# Embedded.net
KiCad netlist of a schematic drawn in EAGLE
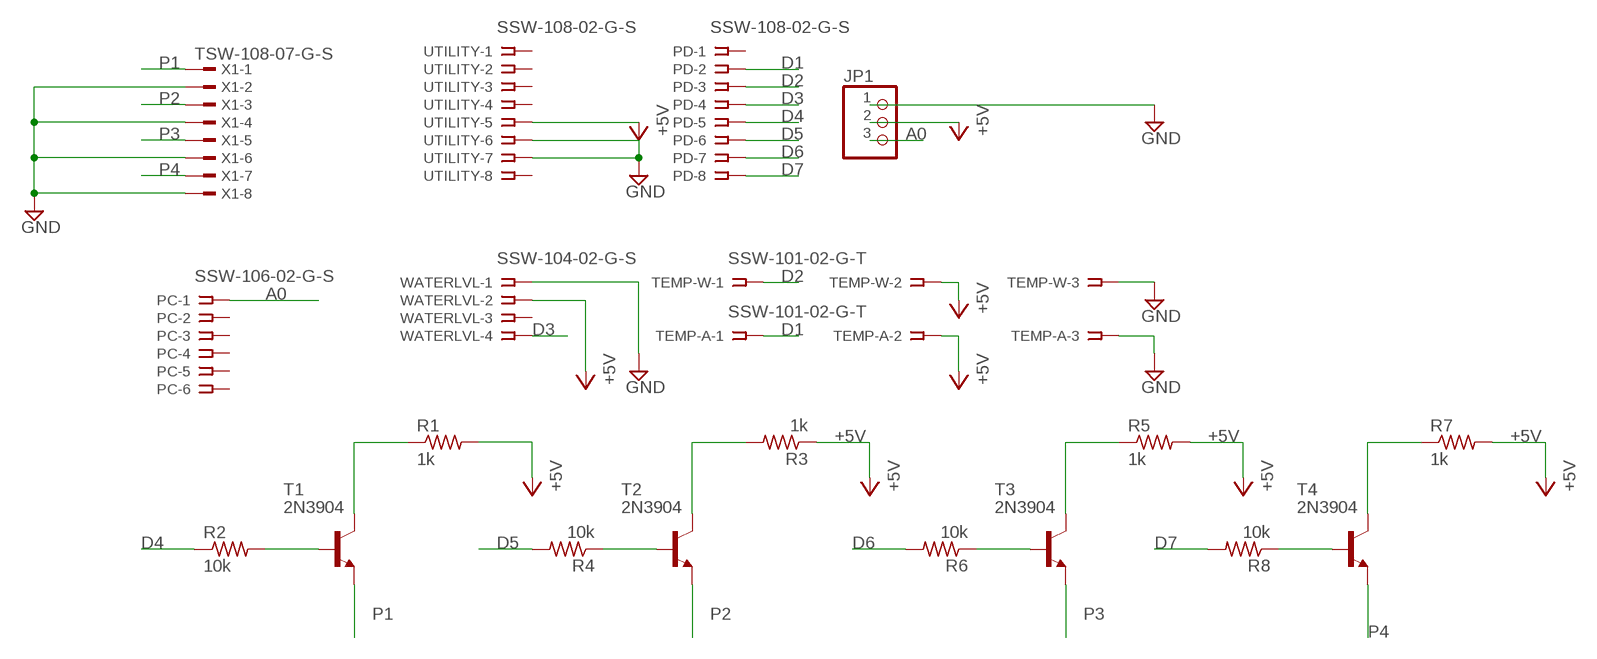
[diagram p0: schematic, sheet 1]

(export (version "E")
  (design (tool "Eeschema 10.0.6"))
  (components
    (comp (ref "JP1")
      (value "PINHD-1X3")
      (footprint "eagle-import:1X03")
      (libsource (lib "eagle-import") (part "PINHD-1X3"))
    )
    (comp (ref "PC")
      (value "SSW-106-02-G-S")
      (footprint "eagle-import:SSW-106-02-G-S")
      (fields (field (name "MF") "Samtec Inc."))
      (libsource (lib "eagle-import") (part "SSW-106-02-G-S"))
    )
    (comp (ref "PD")
      (value "SSW-108-02-G-S")
      (footprint "eagle-import:SSW-108-02-G-S")
      (fields (field (name "MF") "Samtec Inc."))
      (libsource (lib "eagle-import") (part "SSW-108-02-G-S"))
    )
    (comp (ref "R1")
      (value "1k")
      (footprint "eagle-import:0411_15")
      (libsource (lib "eagle-import") (part "RESISTOR"))
    )
    (comp (ref "R2")
      (value "10k")
      (footprint "eagle-import:0411_15")
      (libsource (lib "eagle-import") (part "RESISTOR"))
    )
    (comp (ref "R3")
      (value "1k")
      (footprint "eagle-import:0411_15")
      (libsource (lib "eagle-import") (part "RESISTOR"))
    )
    (comp (ref "R4")
      (value "10k")
      (footprint "eagle-import:0411_15")
      (libsource (lib "eagle-import") (part "RESISTOR"))
    )
    (comp (ref "R5")
      (value "1k")
      (footprint "eagle-import:0411_15")
      (libsource (lib "eagle-import") (part "RESISTOR"))
    )
    (comp (ref "R6")
      (value "10k")
      (footprint "eagle-import:0411_15")
      (libsource (lib "eagle-import") (part "RESISTOR"))
    )
    (comp (ref "R7")
      (value "1k")
      (footprint "eagle-import:0411_15")
      (libsource (lib "eagle-import") (part "RESISTOR"))
    )
    (comp (ref "R8")
      (value "10k")
      (footprint "eagle-import:0411_15")
      (libsource (lib "eagle-import") (part "RESISTOR"))
    )
    (comp (ref "T1")
      (value "2N3904")
      (footprint "eagle-import:TO92")
      (libsource (lib "eagle-import") (part "2N3904"))
    )
    (comp (ref "T2")
      (value "2N3904")
      (footprint "eagle-import:TO92")
      (libsource (lib "eagle-import") (part "2N3904"))
    )
    (comp (ref "T3")
      (value "2N3904")
      (footprint "eagle-import:TO92")
      (libsource (lib "eagle-import") (part "2N3904"))
    )
    (comp (ref "T4")
      (value "2N3904")
      (footprint "eagle-import:TO92")
      (libsource (lib "eagle-import") (part "2N3904"))
    )
    (comp (ref "TEMP-A")
      (value "SSW-101-02-G-T")
      (footprint "eagle-import:SSW-101-02-G-T")
      (fields (field (name "MF") "Samtec Inc."))
      (libsource (lib "eagle-import") (part "SSW-101-02-G-T"))
    )
    (comp (ref "TEMP-W")
      (value "SSW-101-02-G-T")
      (footprint "eagle-import:SSW-101-02-G-T")
      (fields (field (name "MF") "Samtec Inc."))
      (libsource (lib "eagle-import") (part "SSW-101-02-G-T"))
    )
    (comp (ref "UTILITY")
      (value "SSW-108-02-G-S")
      (footprint "eagle-import:SSW-108-02-G-S")
      (fields (field (name "MF") "Samtec Inc."))
      (libsource (lib "eagle-import") (part "SSW-108-02-G-S"))
    )
    (comp (ref "WATERLVL")
      (value "SSW-104-02-G-S")
      (footprint "eagle-import:SSW-104-02-G-S")
      (fields (field (name "MF") "Samtec Inc."))
      (libsource (lib "eagle-import") (part "SSW-104-02-G-S"))
    )
    (comp (ref "X1")
      (value "TSW-108-07-G-S")
      (footprint "eagle-import:TSW-108-XX-G-S")
      (fields (field (name "MF") "Samtec Inc."))
      (libsource (lib "eagle-import") (part "TSW-108--G-S07"))
    )
  )
  (nets
    (net (code "1") (name "+5V") (class "Default")
      (node (ref "JP1") (pin "2") (pinfunction "2_2") (pintype "passive"))
      (node (ref "R1") (pin "2") (pinfunction "2_2") (pintype "passive"))
      (node (ref "R3") (pin "1") (pinfunction "1_1") (pintype "passive"))
      (node (ref "R5") (pin "2") (pinfunction "2_2") (pintype "passive"))
      (node (ref "R7") (pin "2") (pinfunction "2_2") (pintype "passive"))
      (node (ref "TEMP-A") (pin "2") (pinfunction "1_2") (pintype "passive"))
      (node (ref "TEMP-W") (pin "2") (pinfunction "1_2") (pintype "passive"))
      (node (ref "UTILITY") (pin "5") (pinfunction "1_5") (pintype "passive"))
      (node (ref "WATERLVL") (pin "2") (pinfunction "1_2") (pintype "passive"))
    )
    (net (code "2") (name "/A0") (class "Default")
      (node (ref "JP1") (pin "3") (pinfunction "3_3") (pintype "passive"))
      (node (ref "PC") (pin "1") (pinfunction "1_1") (pintype "passive"))
    )
    (net (code "3") (name "/D1") (class "Default")
      (node (ref "PD") (pin "2") (pinfunction "1_2") (pintype "passive"))
      (node (ref "TEMP-A") (pin "1") (pinfunction "1_1") (pintype "passive"))
    )
    (net (code "4") (name "/D2") (class "Default")
      (node (ref "PD") (pin "3") (pinfunction "1_3") (pintype "passive"))
      (node (ref "TEMP-W") (pin "1") (pinfunction "1_1") (pintype "passive"))
    )
    (net (code "5") (name "/D3") (class "Default")
      (node (ref "PD") (pin "4") (pinfunction "1_4") (pintype "passive"))
      (node (ref "WATERLVL") (pin "4") (pinfunction "1_4") (pintype "passive"))
    )
    (net (code "6") (name "/D4") (class "Default")
      (node (ref "PD") (pin "5") (pinfunction "1_5") (pintype "passive"))
      (node (ref "R2") (pin "1") (pinfunction "1_1") (pintype "passive"))
    )
    (net (code "7") (name "/D5") (class "Default")
      (node (ref "PD") (pin "6") (pinfunction "1_6") (pintype "passive"))
      (node (ref "R4") (pin "2") (pinfunction "2_2") (pintype "passive"))
    )
    (net (code "8") (name "/D6") (class "Default")
      (node (ref "PD") (pin "7") (pinfunction "1_7") (pintype "passive"))
      (node (ref "R6") (pin "2") (pinfunction "2_2") (pintype "passive"))
    )
    (net (code "9") (name "/D7") (class "Default")
      (node (ref "PD") (pin "8") (pinfunction "1_8") (pintype "passive"))
      (node (ref "R8") (pin "2") (pinfunction "2_2") (pintype "passive"))
    )
    (net (code "10") (name "/P1") (class "Default")
      (node (ref "T1") (pin "3") (pinfunction "E_3") (pintype "passive"))
      (node (ref "X1") (pin "1") (pinfunction "1_1") (pintype "passive"))
    )
    (net (code "11") (name "/P2") (class "Default")
      (node (ref "T2") (pin "3") (pinfunction "E_3") (pintype "passive"))
      (node (ref "X1") (pin "3") (pinfunction "1_3") (pintype "passive"))
    )
    (net (code "12") (name "/P3") (class "Default")
      (node (ref "T3") (pin "3") (pinfunction "E_3") (pintype "passive"))
      (node (ref "X1") (pin "5") (pinfunction "1_5") (pintype "passive"))
    )
    (net (code "13") (name "/P4") (class "Default")
      (node (ref "T4") (pin "3") (pinfunction "E_3") (pintype "passive"))
      (node (ref "X1") (pin "7") (pinfunction "1_7") (pintype "passive"))
    )
    (net (code "14") (name "GND") (class "Default")
      (node (ref "JP1") (pin "1") (pinfunction "1_1") (pintype "passive"))
      (node (ref "TEMP-A") (pin "3") (pinfunction "1_3") (pintype "passive"))
      (node (ref "TEMP-W") (pin "3") (pinfunction "1_3") (pintype "passive"))
      (node (ref "UTILITY") (pin "6") (pinfunction "1_6") (pintype "passive"))
      (node (ref "UTILITY") (pin "7") (pinfunction "1_7") (pintype "passive"))
      (node (ref "WATERLVL") (pin "1") (pinfunction "1_1") (pintype "passive"))
      (node (ref "X1") (pin "2") (pinfunction "1_2") (pintype "passive"))
      (node (ref "X1") (pin "4") (pinfunction "1_4") (pintype "passive"))
      (node (ref "X1") (pin "6") (pinfunction "1_6") (pintype "passive"))
      (node (ref "X1") (pin "8") (pinfunction "1_8") (pintype "passive"))
    )
    (net (code "15") (name "Net-(T1-B)") (class "Default")
      (node (ref "R2") (pin "2") (pinfunction "2_2") (pintype "passive"))
      (node (ref "T1") (pin "2") (pinfunction "B_2") (pintype "passive"))
    )
    (net (code "16") (name "Net-(T1-C)") (class "Default")
      (node (ref "R1") (pin "1") (pinfunction "1_1") (pintype "passive"))
      (node (ref "T1") (pin "1") (pinfunction "C_1") (pintype "passive"))
    )
    (net (code "17") (name "Net-(T2-B)") (class "Default")
      (node (ref "R4") (pin "1") (pinfunction "1_1") (pintype "passive"))
      (node (ref "T2") (pin "2") (pinfunction "B_2") (pintype "passive"))
    )
    (net (code "18") (name "Net-(T2-C)") (class "Default")
      (node (ref "R3") (pin "2") (pinfunction "2_2") (pintype "passive"))
      (node (ref "T2") (pin "1") (pinfunction "C_1") (pintype "passive"))
    )
    (net (code "19") (name "Net-(T3-B)") (class "Default")
      (node (ref "R6") (pin "1") (pinfunction "1_1") (pintype "passive"))
      (node (ref "T3") (pin "2") (pinfunction "B_2") (pintype "passive"))
    )
    (net (code "20") (name "Net-(T3-C)") (class "Default")
      (node (ref "R5") (pin "1") (pinfunction "1_1") (pintype "passive"))
      (node (ref "T3") (pin "1") (pinfunction "C_1") (pintype "passive"))
    )
    (net (code "21") (name "Net-(T4-B)") (class "Default")
      (node (ref "R8") (pin "1") (pinfunction "1_1") (pintype "passive"))
      (node (ref "T4") (pin "2") (pinfunction "B_2") (pintype "passive"))
    )
    (net (code "22") (name "Net-(T4-C)") (class "Default")
      (node (ref "R7") (pin "1") (pinfunction "1_1") (pintype "passive"))
      (node (ref "T4") (pin "1") (pinfunction "C_1") (pintype "passive"))
    )
    (net (code "23") (name "unconnected-(PCB-1-Pad2)") (class "Default")
      (node (ref "PC") (pin "2") (pinfunction "1_2") (pintype "passive"))
    )
    (net (code "24") (name "unconnected-(PCC-1-Pad3)") (class "Default")
      (node (ref "PC") (pin "3") (pinfunction "1_3") (pintype "passive"))
    )
    (net (code "25") (name "unconnected-(PCD-1-Pad4)") (class "Default")
      (node (ref "PC") (pin "4") (pinfunction "1_4") (pintype "passive"))
    )
    (net (code "26") (name "unconnected-(PCE-1-Pad5)") (class "Default")
      (node (ref "PC") (pin "5") (pinfunction "1_5") (pintype "passive"))
    )
    (net (code "27") (name "unconnected-(PCF-1-Pad6)") (class "Default")
      (node (ref "PC") (pin "6") (pinfunction "1_6") (pintype "passive"))
    )
    (net (code "28") (name "unconnected-(PD-Pad1)") (class "Default")
      (node (ref "PD") (pin "1") (pinfunction "1_1") (pintype "passive"))
    )
    (net (code "29") (name "unconnected-(UTILITY-Pad1)") (class "Default")
      (node (ref "UTILITY") (pin "1") (pinfunction "1_1") (pintype "passive"))
    )
    (net (code "30") (name "unconnected-(UTILITYB-1-Pad2)") (class "Default")
      (node (ref "UTILITY") (pin "2") (pinfunction "1_2") (pintype "passive"))
    )
    (net (code "31") (name "unconnected-(UTILITYC-1-Pad3)") (class "Default")
      (node (ref "UTILITY") (pin "3") (pinfunction "1_3") (pintype "passive"))
    )
    (net (code "32") (name "unconnected-(UTILITYD-1-Pad4)") (class "Default")
      (node (ref "UTILITY") (pin "4") (pinfunction "1_4") (pintype "passive"))
    )
    (net (code "33") (name "unconnected-(UTILITYH-1-Pad8)") (class "Default")
      (node (ref "UTILITY") (pin "8") (pinfunction "1_8") (pintype "passive"))
    )
    (net (code "34") (name "unconnected-(WATERLVLC-1-Pad3)") (class "Default")
      (node (ref "WATERLVL") (pin "3") (pinfunction "1_3") (pintype "passive"))
    )
  )
)
